# MCU.net
KiCad netlist of a schematic drawn in Altium Designer
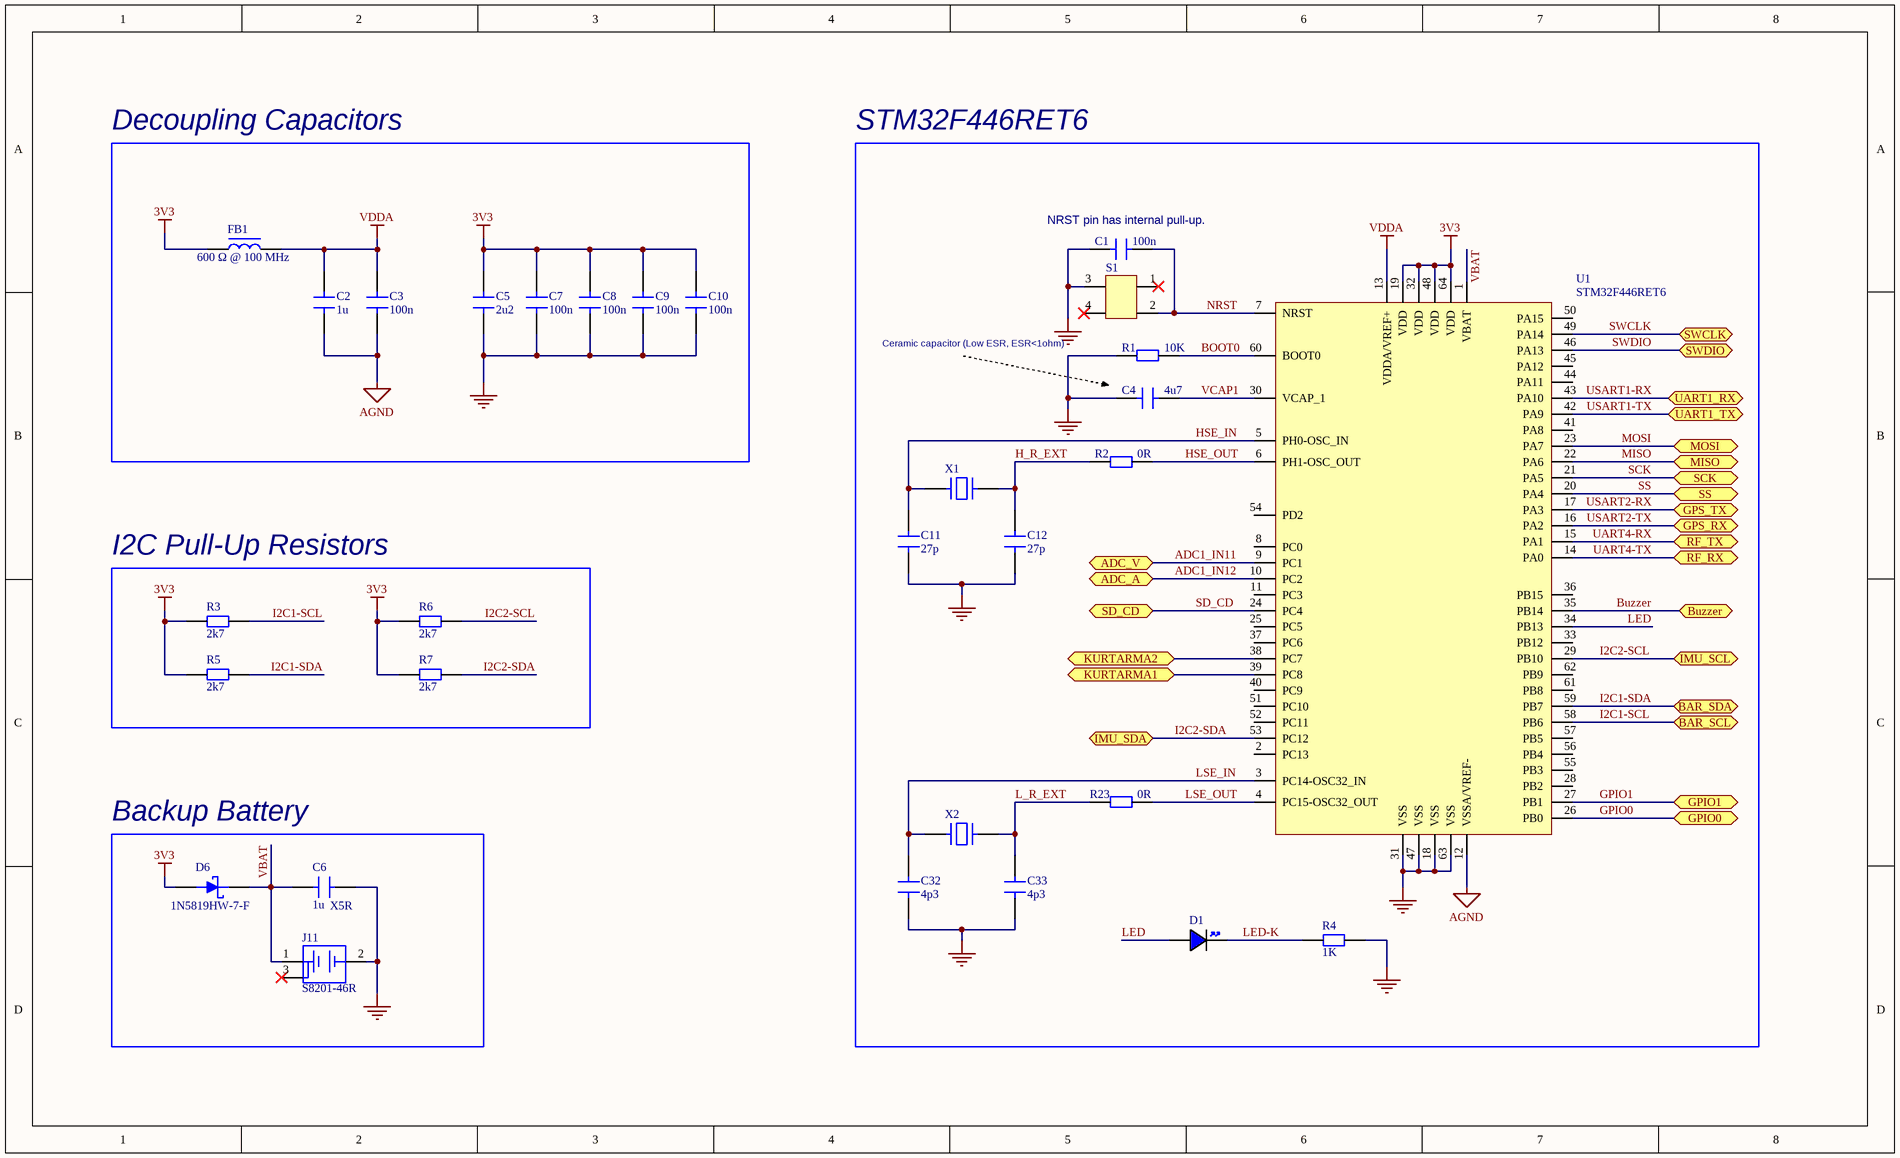
[diagram p0: MCU.SchDoc]

(export (version "E")
  (design (tool "Eeschema 10.0.6"))
  (components
    (comp (ref "C1")
      (value "100n")
      (footprint "CAP 0603")
      (description "Capacitor SMD 0603 50V")
      (libsource (lib "Schlib") (part "CAP 0603 50V"))
    )
    (comp (ref "C2")
      (value "1u")
      (footprint "CAP 0805")
      (description "Capacitor SMD 0805 50V")
      (libsource (lib "Schlib") (part "CAP 0805 50V"))
    )
    (comp (ref "C3")
      (value "100n")
      (footprint "CAP 0603")
      (description "Capacitor SMD 0603 50V")
      (libsource (lib "Schlib") (part "CAP 0603 50V"))
    )
    (comp (ref "C4")
      (value "4u7")
      (footprint "CAP 0805")
      (description "Capacitor SMD 0805 25V")
      (libsource (lib "Schlib") (part "CAP 0805 25V"))
    )
    (comp (ref "C5")
      (value "2u2")
      (footprint "CAP 0805")
      (description "Capacitor SMD 0805 25V")
      (libsource (lib "Schlib") (part "CAP 0805 25V"))
    )
    (comp (ref "C6")
      (value "1u")
      (footprint "CAP 0603")
      (description "Capacitor SMD 0603 16V")
      (libsource (lib "Schlib") (part "CAP 0603 16V"))
    )
    (comp (ref "C7")
      (value "100n")
      (footprint "CAP 0603")
      (description "Capacitor SMD 0603 50V")
      (libsource (lib "Schlib") (part "CAP 0603 50V"))
    )
    (comp (ref "C8")
      (value "100n")
      (footprint "CAP 0603")
      (description "Capacitor SMD 0603 50V")
      (libsource (lib "Schlib") (part "CAP 0603 50V"))
    )
    (comp (ref "C9")
      (value "100n")
      (footprint "CAP 0603")
      (description "Capacitor SMD 0603 50V")
      (libsource (lib "Schlib") (part "CAP 0603 50V"))
    )
    (comp (ref "C10")
      (value "100n")
      (footprint "CAP 0603")
      (description "Capacitor SMD 0603 50V")
      (libsource (lib "Schlib") (part "CAP 0603 50V"))
    )
    (comp (ref "C11")
      (value "27p")
      (footprint "CAP 0603")
      (description "Capacitor SMD 0603 50V")
      (libsource (lib "Schlib") (part "CAP 0603 50V"))
    )
    (comp (ref "C12")
      (value "27p")
      (footprint "CAP 0603")
      (description "Capacitor SMD 0603 50V")
      (libsource (lib "Schlib") (part "CAP 0603 50V"))
    )
    (comp (ref "C32")
      (value "4p3")
      (footprint "CAP 0603")
      (description "Capacitor SMD 0603 50V")
      (libsource (lib "Schlib") (part "CAP 0603 50V"))
    )
    (comp (ref "C33")
      (value "4p3")
      (footprint "CAP 0603")
      (description "Capacitor SMD 0603 50V")
      (libsource (lib "Schlib") (part "CAP 0603 50V"))
    )
    (comp (ref "D1")
      (value "LED 0805 BLUE")
      (footprint "LED 0805 BLUE")
      (description "LED 0805 BLUE SMD")
      (libsource (lib "Schlib") (part "LED 0805 BLUE"))
    )
    (comp (ref "D6")
      (value "1N5819HW-7-F")
      (footprint "1N5819HW-7-F")
      (description "Rectifier Diode, Schottky, 1 Phase, 1 Element, 1A, 40V V(RRM), Silicon")
      (fields (field (name "MANUFACTURER") "Diodes"))
      (libsource (lib "Schlib") (part "1N5819HW-7-F"))
    )
    (comp (ref "FB1")
      (value "600 Ω @ 100 MHz")
      (footprint "FB 0805")
      (description "Ferrite Bead SMD 0805")
      (libsource (lib "Schlib") (part "FB 0805"))
    )
    (comp (ref "J11")
      (value "S8201-46R")
      (footprint "S8201-46R")
      (description "Battery Holder, Coin Cell, 1225, Smd Rohs Compliant: Yes ¦Harwin S8201-46R")
      (fields (field (name "MANUFACTURER") "Harwin"))
      (libsource (lib "Schlib") (part "S8201-46R"))
    )
    (comp (ref "R1")
      (value "10K")
      (footprint "RES 0603")
      (description "Resistor SMD 0603")
      (libsource (lib "Schlib") (part "RES 0603"))
    )
    (comp (ref "R2")
      (value "0R")
      (footprint "RES 0603")
      (description "Resistor SMD 0603")
      (libsource (lib "Schlib") (part "RES 0603"))
    )
    (comp (ref "R3")
      (value "2k7")
      (footprint "RES 0603")
      (description "Resistor SMD 0603")
      (libsource (lib "Schlib") (part "RES 0603"))
    )
    (comp (ref "R4")
      (value "1K")
      (footprint "RES 0603")
      (description "Resistor SMD 0603")
      (libsource (lib "Schlib") (part "RES 0603"))
    )
    (comp (ref "R5")
      (value "2k7")
      (footprint "RES 0603")
      (description "Resistor SMD 0603")
      (libsource (lib "Schlib") (part "RES 0603"))
    )
    (comp (ref "R6")
      (value "2k7")
      (footprint "RES 0603")
      (description "Resistor SMD 0603")
      (libsource (lib "Schlib") (part "RES 0603"))
    )
    (comp (ref "R7")
      (value "2k7")
      (footprint "RES 0603")
      (description "Resistor SMD 0603")
      (libsource (lib "Schlib") (part "RES 0603"))
    )
    (comp (ref "R23")
      (value "0R")
      (footprint "RES 0603")
      (description "Resistor SMD 0603")
      (libsource (lib "Schlib") (part "RES 0603"))
    )
    (comp (ref "S1")
      (value "FSM4JSMATR")
      (footprint "FSM4JSMATR")
      (description "Switch Tactile OFF (ON) SPST Round Button Gull Wing 0.05A 24VDC 1.57N SMD T/R")
      (fields (field (name "MANUFACTURER") "TE Connectivity Alcoswitch"))
      (libsource (lib "Schlib") (part "FSM4JSMATR"))
    )
    (comp (ref "U1")
      (value "STM32F446RET6")
      (footprint "STM32F446RET6")
      (description "ARM® Cortex®-M4 STM32 F4 Microcontroller IC 32-Bit 180MHz 512KB (512K x 8) FLASH 64-LQFP (10x10)")
      (fields (field (name "MANUFACTURER") "STMicroelectronics"))
      (libsource (lib "Schlib") (part "STM32F446RET6"))
    )
    (comp (ref "X1")
      (value "ABM3-8.000MHZ-D2Y-T")
      (footprint "ABM3-8.000MHZ-D2Y-T")
      (description "Crystal 8MHz ±20ppm (Tol) ±30ppm (Stability) 18pF FUND 140Ohm 2-Pin Mini-CSMD T/R")
      (fields (field (name "MANUFACTURER") "Abracon"))
      (libsource (lib "Schlib") (part "ABM3-8.000MHZ-D2Y-T"))
    )
    (comp (ref "X2")
      (value "ABS25-32.768KHZ-6-T")
      (footprint "ABS25-32.768KHZ-6-T")
      (description "Crystal, Plastic Molded 32.768Khz, 6Pf, 20Ppm-40+85C, 8 X 3.8 X 2.5 Rohs Compliant: Yes")
      (fields (field (name "MANUFACTURER") "Abracon"))
      (libsource (lib "Schlib") (part "ABS25-32.768KHZ-6-T"))
    )
  )
  (nets
    (net (code "1") (name "/ADC1_IN11") (class "Default")
      (node (ref "U1") (pin "9") (pinfunction "PC1_9") (pintype "passive"))
    )
    (net (code "2") (name "/ADC1_IN12") (class "Default")
      (node (ref "U1") (pin "10") (pinfunction "PC2_10") (pintype "passive"))
    )
    (net (code "3") (name "/BOOT0") (class "Default")
      (node (ref "R1") (pin "2") (pinfunction "2_2") (pintype "passive"))
      (node (ref "U1") (pin "60") (pinfunction "BOOT0_60") (pintype "passive"))
    )
    (net (code "4") (name "/Buzzer") (class "Default")
      (node (ref "U1") (pin "35") (pinfunction "PB14_35") (pintype "passive"))
    )
    (net (code "5") (name "/GPIO0") (class "Default")
      (node (ref "U1") (pin "26") (pinfunction "PB0_26") (pintype "passive"))
    )
    (net (code "6") (name "/GPIO1") (class "Default")
      (node (ref "U1") (pin "27") (pinfunction "PB1_27") (pintype "passive"))
    )
    (net (code "7") (name "/HSE_IN") (class "Default")
      (node (ref "C11") (pin "2") (pinfunction "2_2") (pintype "passive"))
      (node (ref "U1") (pin "5") (pinfunction "PH0-OSC_IN_5") (pintype "passive"))
      (node (ref "X1") (pin "1") (pinfunction "1_1") (pintype "passive"))
    )
    (net (code "8") (name "/HSE_OUT") (class "Default")
      (node (ref "R2") (pin "2") (pinfunction "2_2") (pintype "passive"))
      (node (ref "U1") (pin "6") (pinfunction "PH1-OSC_OUT_6") (pintype "passive"))
    )
    (net (code "9") (name "/H_R_EXT") (class "Default")
      (node (ref "C12") (pin "2") (pinfunction "2_2") (pintype "passive"))
      (node (ref "R2") (pin "1") (pinfunction "1_1") (pintype "passive"))
      (node (ref "X1") (pin "2") (pinfunction "2_2") (pintype "passive"))
    )
    (net (code "10") (name "/I2C1-SCL") (class "Default")
      (node (ref "R3") (pin "1") (pinfunction "1_1") (pintype "passive"))
      (node (ref "U1") (pin "58") (pinfunction "PB6_58") (pintype "passive"))
    )
    (net (code "11") (name "/I2C1-SDA") (class "Default")
      (node (ref "R5") (pin "1") (pinfunction "1_1") (pintype "passive"))
      (node (ref "U1") (pin "59") (pinfunction "PB7_59") (pintype "passive"))
    )
    (net (code "12") (name "/I2C2-SCL") (class "Default")
      (node (ref "R6") (pin "1") (pinfunction "1_1") (pintype "passive"))
      (node (ref "U1") (pin "29") (pinfunction "PB10_29") (pintype "passive"))
    )
    (net (code "13") (name "/I2C2-SDA") (class "Default")
      (node (ref "R7") (pin "1") (pinfunction "1_1") (pintype "passive"))
      (node (ref "U1") (pin "53") (pinfunction "PC12_53") (pintype "passive"))
    )
    (net (code "14") (name "/KURTARMA1") (class "Default")
      (node (ref "U1") (pin "39") (pinfunction "PC8_39") (pintype "passive"))
    )
    (net (code "15") (name "/KURTARMA2") (class "Default")
      (node (ref "U1") (pin "38") (pinfunction "PC7_38") (pintype "passive"))
    )
    (net (code "16") (name "/LED") (class "Default")
      (node (ref "D1") (pin "A") (pinfunction "A_A") (pintype "passive"))
      (node (ref "U1") (pin "34") (pinfunction "PB13_34") (pintype "passive"))
    )
    (net (code "17") (name "/LED-K") (class "Default")
      (node (ref "D1") (pin "K") (pinfunction "K_K") (pintype "passive"))
      (node (ref "R4") (pin "1") (pinfunction "1_1") (pintype "passive"))
    )
    (net (code "18") (name "/LSE_IN") (class "Default")
      (node (ref "C32") (pin "2") (pinfunction "2_2") (pintype "passive"))
      (node (ref "U1") (pin "3") (pinfunction "PC14-OSC32_IN_3") (pintype "passive"))
      (node (ref "X2") (pin "1") (pinfunction "1_1") (pintype "passive"))
    )
    (net (code "19") (name "/LSE_OUT") (class "Default")
      (node (ref "R23") (pin "2") (pinfunction "2_2") (pintype "passive"))
      (node (ref "U1") (pin "4") (pinfunction "PC15-OSC32_OUT_4") (pintype "passive"))
    )
    (net (code "20") (name "/L_R_EXT") (class "Default")
      (node (ref "C33") (pin "2") (pinfunction "2_2") (pintype "passive"))
      (node (ref "R23") (pin "1") (pinfunction "1_1") (pintype "passive"))
      (node (ref "X2") (pin "4") (pinfunction "4_4") (pintype "passive"))
    )
    (net (code "21") (name "/MISO") (class "Default")
      (node (ref "U1") (pin "22") (pinfunction "PA6_22") (pintype "passive"))
    )
    (net (code "22") (name "/MOSI") (class "Default")
      (node (ref "U1") (pin "23") (pinfunction "PA7_23") (pintype "passive"))
    )
    (net (code "23") (name "/NRST") (class "Default")
      (node (ref "C1") (pin "2") (pinfunction "2_2") (pintype "passive"))
      (node (ref "S1") (pin "2") (pinfunction "2_2") (pintype "passive"))
      (node (ref "U1") (pin "7") (pinfunction "NRST_7") (pintype "passive"))
    )
    (net (code "24") (name "/SCK") (class "Default")
      (node (ref "U1") (pin "21") (pinfunction "PA5_21") (pintype "passive"))
    )
    (net (code "25") (name "/SD_CD") (class "Default")
      (node (ref "U1") (pin "24") (pinfunction "PC4_24") (pintype "passive"))
    )
    (net (code "26") (name "/SS") (class "Default")
      (node (ref "U1") (pin "20") (pinfunction "PA4_20") (pintype "passive"))
    )
    (net (code "27") (name "/SWCLK") (class "Default")
      (node (ref "U1") (pin "49") (pinfunction "PA14_49") (pintype "passive"))
    )
    (net (code "28") (name "/SWDIO") (class "Default")
      (node (ref "U1") (pin "46") (pinfunction "PA13_46") (pintype "passive"))
    )
    (net (code "29") (name "/UART4-RX") (class "Default")
      (node (ref "U1") (pin "15") (pinfunction "PA1_15") (pintype "passive"))
    )
    (net (code "30") (name "/UART4-TX") (class "Default")
      (node (ref "U1") (pin "14") (pinfunction "PA0_14") (pintype "passive"))
    )
    (net (code "31") (name "/USART1-RX") (class "Default")
      (node (ref "U1") (pin "43") (pinfunction "PA10_43") (pintype "passive"))
    )
    (net (code "32") (name "/USART1-TX") (class "Default")
      (node (ref "U1") (pin "42") (pinfunction "PA9_42") (pintype "passive"))
    )
    (net (code "33") (name "/USART2-RX") (class "Default")
      (node (ref "U1") (pin "17") (pinfunction "PA3_17") (pintype "passive"))
    )
    (net (code "34") (name "/USART2-TX") (class "Default")
      (node (ref "U1") (pin "16") (pinfunction "PA2_16") (pintype "passive"))
    )
    (net (code "35") (name "/VBAT") (class "Default")
      (node (ref "C6") (pin "2") (pinfunction "2_2") (pintype "passive"))
      (node (ref "D6") (pin "A") (pintype "passive"))
      (node (ref "J11") (pin "1") (pinfunction "+_1") (pintype "passive"))
      (node (ref "U1") (pin "1") (pinfunction "VBAT_1") (pintype "passive"))
    )
    (net (code "36") (name "/VCAP1") (class "Default")
      (node (ref "C4") (pin "2") (pinfunction "2_2") (pintype "passive"))
      (node (ref "U1") (pin "30") (pinfunction "VCAP_1_30") (pintype "passive"))
    )
    (net (code "37") (name "3V3") (class "Default")
      (node (ref "C10") (pin "2") (pinfunction "2_2") (pintype "passive"))
      (node (ref "C5") (pin "2") (pinfunction "2_2") (pintype "passive"))
      (node (ref "C7") (pin "2") (pinfunction "2_2") (pintype "passive"))
      (node (ref "C8") (pin "2") (pinfunction "2_2") (pintype "passive"))
      (node (ref "C9") (pin "2") (pinfunction "2_2") (pintype "passive"))
      (node (ref "D6") (pin "C") (pintype "passive"))
      (node (ref "FB1") (pin "1") (pintype "passive"))
      (node (ref "R3") (pin "2") (pinfunction "2_2") (pintype "passive"))
      (node (ref "R5") (pin "2") (pinfunction "2_2") (pintype "passive"))
      (node (ref "R6") (pin "2") (pinfunction "2_2") (pintype "passive"))
      (node (ref "R7") (pin "2") (pinfunction "2_2") (pintype "passive"))
      (node (ref "U1") (pin "19") (pinfunction "VDD_19") (pintype "passive"))
      (node (ref "U1") (pin "32") (pinfunction "VDD_32") (pintype "passive"))
      (node (ref "U1") (pin "48") (pinfunction "VDD_48") (pintype "passive"))
      (node (ref "U1") (pin "64") (pinfunction "VDD_64") (pintype "passive"))
    )
    (net (code "38") (name "AGND") (class "Default")
      (node (ref "C2") (pin "1") (pinfunction "1_1") (pintype "passive"))
      (node (ref "C3") (pin "1") (pinfunction "1_1") (pintype "passive"))
      (node (ref "U1") (pin "12") (pinfunction "VSSA/VREF-_12") (pintype "passive"))
    )
    (net (code "39") (name "GND") (class "Default")
      (node (ref "C1") (pin "1") (pinfunction "1_1") (pintype "passive"))
      (node (ref "C10") (pin "1") (pinfunction "1_1") (pintype "passive"))
      (node (ref "C11") (pin "1") (pinfunction "1_1") (pintype "passive"))
      (node (ref "C12") (pin "1") (pinfunction "1_1") (pintype "passive"))
      (node (ref "C32") (pin "1") (pinfunction "1_1") (pintype "passive"))
      (node (ref "C33") (pin "1") (pinfunction "1_1") (pintype "passive"))
      (node (ref "C4") (pin "1") (pinfunction "1_1") (pintype "passive"))
      (node (ref "C5") (pin "1") (pinfunction "1_1") (pintype "passive"))
      (node (ref "C6") (pin "1") (pinfunction "1_1") (pintype "passive"))
      (node (ref "C7") (pin "1") (pinfunction "1_1") (pintype "passive"))
      (node (ref "C8") (pin "1") (pinfunction "1_1") (pintype "passive"))
      (node (ref "C9") (pin "1") (pinfunction "1_1") (pintype "passive"))
      (node (ref "J11") (pin "2") (pinfunction "-_2") (pintype "passive"))
      (node (ref "R1") (pin "1") (pinfunction "1_1") (pintype "passive"))
      (node (ref "R4") (pin "2") (pinfunction "2_2") (pintype "passive"))
      (node (ref "S1") (pin "3") (pinfunction "3_3") (pintype "passive"))
      (node (ref "U1") (pin "18") (pinfunction "VSS_18") (pintype "passive"))
      (node (ref "U1") (pin "31") (pinfunction "VSS_31") (pintype "passive"))
      (node (ref "U1") (pin "47") (pinfunction "VSS_47") (pintype "passive"))
      (node (ref "U1") (pin "63") (pinfunction "VSS_63") (pintype "passive"))
    )
    (net (code "40") (name "VDDA") (class "Default")
      (node (ref "C2") (pin "2") (pinfunction "2_2") (pintype "passive"))
      (node (ref "C3") (pin "2") (pinfunction "2_2") (pintype "passive"))
      (node (ref "FB1") (pin "2") (pintype "passive"))
      (node (ref "U1") (pin "13") (pinfunction "VDDA/VREF+_13") (pintype "passive"))
    )
    (net (code "41") (name "unconnected-(J11-+-Pad3)") (class "Default")
      (node (ref "J11") (pin "3") (pinfunction "+_3") (pintype "passive+no_connect"))
    )
    (net (code "42") (name "unconnected-(S1-Pad1)") (class "Default")
      (node (ref "S1") (pin "1") (pinfunction "1_1") (pintype "passive+no_connect"))
    )
    (net (code "43") (name "unconnected-(S1-Pad4)") (class "Default")
      (node (ref "S1") (pin "4") (pinfunction "4_4") (pintype "passive+no_connect"))
    )
    (net (code "44") (name "unconnected-(U1-PA8-Pad41)") (class "Default")
      (node (ref "U1") (pin "41") (pinfunction "PA8_41") (pintype "passive"))
    )
    (net (code "45") (name "unconnected-(U1-PA11-Pad44)") (class "Default")
      (node (ref "U1") (pin "44") (pinfunction "PA11_44") (pintype "passive"))
    )
    (net (code "46") (name "unconnected-(U1-PA12-Pad45)") (class "Default")
      (node (ref "U1") (pin "45") (pinfunction "PA12_45") (pintype "passive"))
    )
    (net (code "47") (name "unconnected-(U1-PA15-Pad50)") (class "Default")
      (node (ref "U1") (pin "50") (pinfunction "PA15_50") (pintype "passive"))
    )
    (net (code "48") (name "unconnected-(U1-PB2-Pad28)") (class "Default")
      (node (ref "U1") (pin "28") (pinfunction "PB2_28") (pintype "passive"))
    )
    (net (code "49") (name "unconnected-(U1-PB3-Pad55)") (class "Default")
      (node (ref "U1") (pin "55") (pinfunction "PB3_55") (pintype "passive"))
    )
    (net (code "50") (name "unconnected-(U1-PB4-Pad56)") (class "Default")
      (node (ref "U1") (pin "56") (pinfunction "PB4_56") (pintype "passive"))
    )
    (net (code "51") (name "unconnected-(U1-PB5-Pad57)") (class "Default")
      (node (ref "U1") (pin "57") (pinfunction "PB5_57") (pintype "passive"))
    )
    (net (code "52") (name "unconnected-(U1-PB8-Pad61)") (class "Default")
      (node (ref "U1") (pin "61") (pinfunction "PB8_61") (pintype "passive"))
    )
    (net (code "53") (name "unconnected-(U1-PB9-Pad62)") (class "Default")
      (node (ref "U1") (pin "62") (pinfunction "PB9_62") (pintype "passive"))
    )
    (net (code "54") (name "unconnected-(U1-PB12-Pad33)") (class "Default")
      (node (ref "U1") (pin "33") (pinfunction "PB12_33") (pintype "passive"))
    )
    (net (code "55") (name "unconnected-(U1-PB15-Pad36)") (class "Default")
      (node (ref "U1") (pin "36") (pinfunction "PB15_36") (pintype "passive"))
    )
    (net (code "56") (name "unconnected-(U1-PC0-Pad8)") (class "Default")
      (node (ref "U1") (pin "8") (pinfunction "PC0_8") (pintype "passive"))
    )
    (net (code "57") (name "unconnected-(U1-PC3-Pad11)") (class "Default")
      (node (ref "U1") (pin "11") (pinfunction "PC3_11") (pintype "passive"))
    )
    (net (code "58") (name "unconnected-(U1-PC5-Pad25)") (class "Default")
      (node (ref "U1") (pin "25") (pinfunction "PC5_25") (pintype "passive"))
    )
    (net (code "59") (name "unconnected-(U1-PC6-Pad37)") (class "Default")
      (node (ref "U1") (pin "37") (pinfunction "PC6_37") (pintype "passive"))
    )
    (net (code "60") (name "unconnected-(U1-PC9-Pad40)") (class "Default")
      (node (ref "U1") (pin "40") (pinfunction "PC9_40") (pintype "passive"))
    )
    (net (code "61") (name "unconnected-(U1-PC10-Pad51)") (class "Default")
      (node (ref "U1") (pin "51") (pinfunction "PC10_51") (pintype "passive"))
    )
    (net (code "62") (name "unconnected-(U1-PC11-Pad52)") (class "Default")
      (node (ref "U1") (pin "52") (pinfunction "PC11_52") (pintype "passive"))
    )
    (net (code "63") (name "unconnected-(U1-PC13-Pad2)") (class "Default")
      (node (ref "U1") (pin "2") (pinfunction "PC13_2") (pintype "passive"))
    )
    (net (code "64") (name "unconnected-(U1-PD2-Pad54)") (class "Default")
      (node (ref "U1") (pin "54") (pinfunction "PD2_54") (pintype "passive"))
    )
  )
)
